# myGlasses.net
KiCad netlist of a schematic drawn in EAGLE
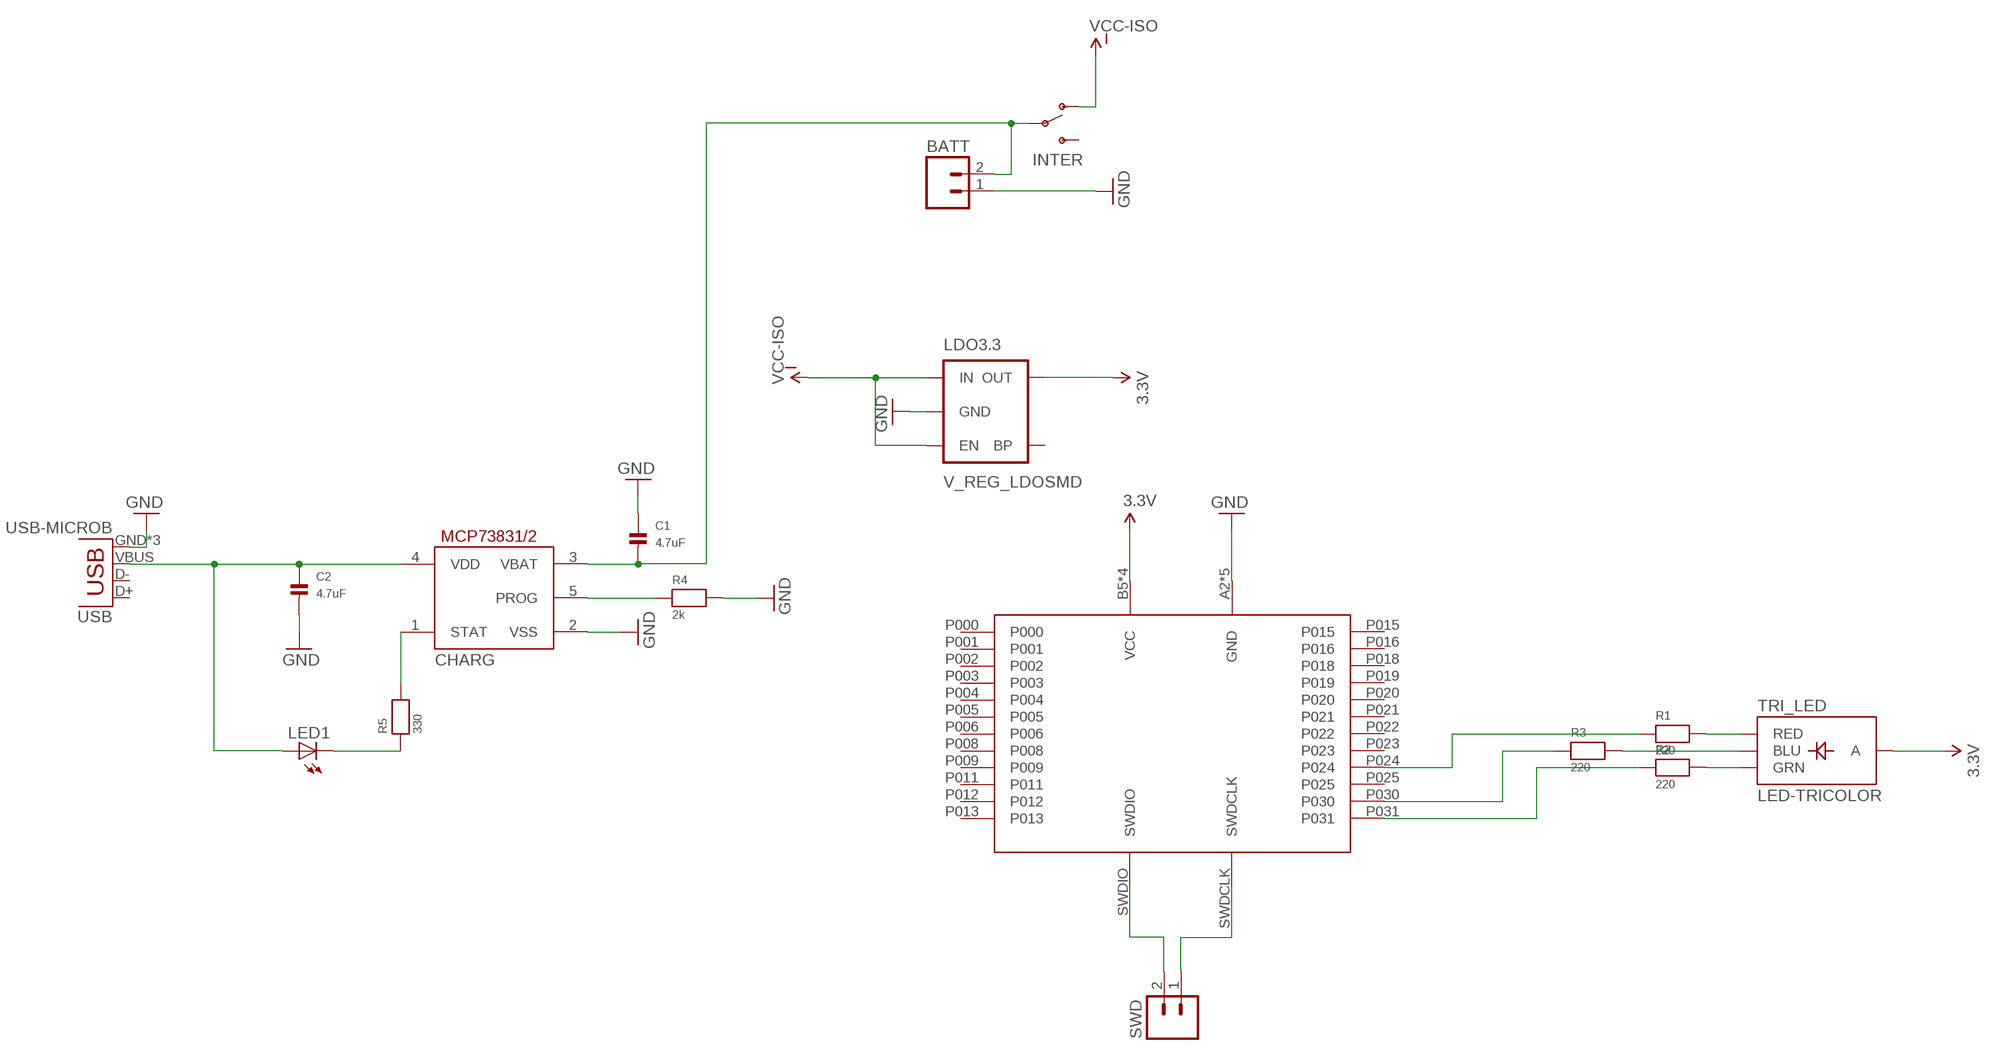
[diagram p0: schematic, sheet 1]

(export (version "E")
  (design (tool "Eeschema 10.0.6"))
  (components
    (comp (ref "BATT")
      (value "M02PTH3")
      (footprint "eagle-import:1X02_LONGPADS")
      (libsource (lib "eagle-import") (part "M02PTH3"))
    )
    (comp (ref "C1")
      (value "4.7uF")
      (footprint "eagle-import:1206")
      (libsource (lib "eagle-import") (part "CAP_CERAMIC1206"))
    )
    (comp (ref "C2")
      (value "4.7uF")
      (footprint "eagle-import:1206")
      (libsource (lib "eagle-import") (part "CAP_CERAMIC1206"))
    )
    (comp (ref "CHARG")
      (value "MCP73831/OT")
      (footprint "eagle-import:SOT23-5L")
      (libsource (lib "eagle-import") (part "MCP73831/OT"))
    )
    (comp (ref "INTER")
      (value "SWITCH-SPDTPTH_LOCK")
      (footprint "eagle-import:SWITCH-SPDT_LOCK.007S")
      (libsource (lib "eagle-import") (part "SWITCH-SPDTPTH_LOCK"))
    )
    (comp (ref "LDO3.3")
      (value "V_REG_LDOSMD")
      (footprint "eagle-import:SOT23-5")
      (libsource (lib "eagle-import") (part "V_REG_LDOSMD"))
    )
    (comp (ref "LED1")
      (value "LEDCHIPLED_1206")
      (footprint "eagle-import:CHIPLED_1206")
      (libsource (lib "eagle-import") (part "LEDCHIPLED_1206"))
    )
    (comp (ref "N550")
      (value "N548")
      (footprint "eagle-import:N548")
      (libsource (lib "eagle-import") (part "N548"))
    )
    (comp (ref "R1")
      (value "220")
      (footprint "eagle-import:1206")
      (libsource (lib "eagle-import") (part "RESISTOR1206"))
    )
    (comp (ref "R2")
      (value "220")
      (footprint "eagle-import:1206")
      (libsource (lib "eagle-import") (part "RESISTOR1206"))
    )
    (comp (ref "R3")
      (value "220")
      (footprint "eagle-import:1206")
      (libsource (lib "eagle-import") (part "RESISTOR1206"))
    )
    (comp (ref "R4")
      (value "2k")
      (footprint "eagle-import:1206")
      (libsource (lib "eagle-import") (part "RESISTOR1206"))
    )
    (comp (ref "R5")
      (value "330")
      (footprint "eagle-import:1206")
      (libsource (lib "eagle-import") (part "RESISTOR1206"))
    )
    (comp (ref "SWD")
      (value "M02PTH")
      (footprint "eagle-import:1X02")
      (libsource (lib "eagle-import") (part "M02PTH"))
    )
    (comp (ref "TRI_LED")
      (value "LED-TRICOLOR")
      (footprint "eagle-import:LED-TRICOLOR-SMD")
      (libsource (lib "eagle-import") (part "LED-TRICOLOR"))
    )
    (comp (ref "USB")
      (value "USB-MICROB")
      (footprint "eagle-import:USB-MICROB")
      (libsource (lib "eagle-import") (part "USB-MICROB"))
    )
  )
  (nets
    (net (code "1") (name "3.3V") (class "Default")
      (node (ref "LDO3.3") (pin "5") (pinfunction "OUT_5") (pintype "passive"))
      (node (ref "N550") (pin "B5") (pinfunction "VCC_B5") (pintype "bidirectional"))
      (node (ref "N550") (pin "B6") (pinfunction "VCC_B6") (pintype "bidirectional"))
      (node (ref "N550") (pin "C5") (pinfunction "VCC_C5") (pintype "bidirectional"))
      (node (ref "N550") (pin "C6") (pinfunction "VCC_C6") (pintype "bidirectional"))
      (node (ref "TRI_LED") (pin "A") (pinfunction "A_A") (pintype "bidirectional"))
    )
    (net (code "2") (name "GND") (class "Default")
      (node (ref "BATT") (pin "1") (pinfunction "1_1") (pintype "passive"))
      (node (ref "C1") (pin "1") (pinfunction "P$1_1") (pintype "passive"))
      (node (ref "C2") (pin "2") (pinfunction "P$2_2") (pintype "passive"))
      (node (ref "CHARG") (pin "2") (pinfunction "VSS_2") (pintype "power_in"))
      (node (ref "LDO3.3") (pin "2") (pinfunction "GND_2") (pintype "input"))
      (node (ref "N550") (pin "A2") (pinfunction "GND_A2") (pintype "bidirectional"))
      (node (ref "N550") (pin "A3") (pinfunction "GND_A3") (pintype "bidirectional"))
      (node (ref "N550") (pin "A4") (pinfunction "GND_A4") (pintype "bidirectional"))
      (node (ref "N550") (pin "A5") (pinfunction "GND_A5") (pintype "bidirectional"))
      (node (ref "N550") (pin "A6") (pinfunction "GND_A6") (pintype "bidirectional"))
      (node (ref "R4") (pin "2") (pinfunction "2_2") (pintype "passive"))
      (node (ref "USB") (pin "GND") (pinfunction "GND_GND") (pintype "bidirectional"))
      (node (ref "USB") (pin "MT1") (pinfunction "GND_MT1") (pintype "bidirectional"))
      (node (ref "USB") (pin "MT2") (pinfunction "GND_MT2") (pintype "bidirectional"))
    )
    (net (code "3") (name "Net-(C1-P$2)") (class "Default")
      (node (ref "BATT") (pin "2") (pinfunction "2_2") (pintype "passive"))
      (node (ref "C1") (pin "2") (pinfunction "P$2_2") (pintype "passive"))
      (node (ref "CHARG") (pin "3") (pinfunction "VBAT_3") (pintype "bidirectional"))
      (node (ref "INTER") (pin "2") (pinfunction "P_2") (pintype "passive"))
    )
    (net (code "4") (name "Net-(C2-P$1)") (class "Default")
      (node (ref "C2") (pin "1") (pinfunction "P$1_1") (pintype "passive"))
      (node (ref "CHARG") (pin "4") (pinfunction "VDD_4") (pintype "power_in"))
      (node (ref "LED1") (pin "A") (pinfunction "A_A") (pintype "passive"))
      (node (ref "USB") (pin "VBUS") (pinfunction "VBUS_VBUS") (pintype "bidirectional"))
    )
    (net (code "5") (name "Net-(CHARG-PROG)") (class "Default")
      (node (ref "CHARG") (pin "5") (pinfunction "PROG_5") (pintype "input"))
      (node (ref "R4") (pin "1") (pinfunction "1_1") (pintype "passive"))
    )
    (net (code "6") (name "Net-(CHARG-STAT)") (class "Default")
      (node (ref "CHARG") (pin "1") (pinfunction "STAT_1") (pintype "output"))
      (node (ref "R5") (pin "2") (pinfunction "2_2") (pintype "passive"))
    )
    (net (code "7") (name "Net-(LED1-PadC)") (class "Default")
      (node (ref "LED1") (pin "C") (pinfunction "C_C") (pintype "passive"))
      (node (ref "R5") (pin "1") (pinfunction "1_1") (pintype "passive"))
    )
    (net (code "8") (name "Net-(N550-PadP024)") (class "Default")
      (node (ref "N550") (pin "P024") (pinfunction "P024_P024") (pintype "bidirectional"))
      (node (ref "R1") (pin "1") (pinfunction "1_1") (pintype "passive"))
    )
    (net (code "9") (name "Net-(N550-PadP030)") (class "Default")
      (node (ref "N550") (pin "P030") (pinfunction "P030_P030") (pintype "bidirectional"))
      (node (ref "R3") (pin "1") (pinfunction "1_1") (pintype "passive"))
    )
    (net (code "10") (name "Net-(N550-PadP031)") (class "Default")
      (node (ref "N550") (pin "P031") (pinfunction "P031_P031") (pintype "bidirectional"))
      (node (ref "R2") (pin "1") (pinfunction "1_1") (pintype "passive"))
    )
    (net (code "11") (name "Net-(N550-PadSWDCLK)") (class "Default")
      (node (ref "N550") (pin "SWDCLK") (pinfunction "SWDCLK_SWDCLK") (pintype "bidirectional"))
      (node (ref "SWD") (pin "1") (pinfunction "1_1") (pintype "passive"))
    )
    (net (code "12") (name "Net-(N550-PadSWDIO)") (class "Default")
      (node (ref "N550") (pin "SWDIO") (pinfunction "SWDIO_SWDIO") (pintype "bidirectional"))
      (node (ref "SWD") (pin "2") (pinfunction "2_2") (pintype "passive"))
    )
    (net (code "13") (name "Net-(TRI_LED-BLU)") (class "Default")
      (node (ref "R3") (pin "2") (pinfunction "2_2") (pintype "passive"))
      (node (ref "TRI_LED") (pin "B") (pinfunction "BLU_B") (pintype "bidirectional"))
    )
    (net (code "14") (name "Net-(TRI_LED-GRN)") (class "Default")
      (node (ref "R2") (pin "2") (pinfunction "2_2") (pintype "passive"))
      (node (ref "TRI_LED") (pin "G") (pinfunction "GRN_G") (pintype "bidirectional"))
    )
    (net (code "15") (name "Net-(TRI_LED-RED)") (class "Default")
      (node (ref "R1") (pin "2") (pinfunction "2_2") (pintype "passive"))
      (node (ref "TRI_LED") (pin "R") (pinfunction "RED_R") (pintype "bidirectional"))
    )
    (net (code "16") (name "VCC-ISO") (class "Default")
      (node (ref "INTER") (pin "1") (pinfunction "O_1") (pintype "passive"))
      (node (ref "LDO3.3") (pin "1") (pinfunction "IN_1") (pintype "input"))
      (node (ref "LDO3.3") (pin "3") (pinfunction "EN_3") (pintype "input"))
    )
    (net (code "17") (name "unconnected-(INTER-S-Pad3)") (class "Default")
      (node (ref "INTER") (pin "3") (pinfunction "S_3") (pintype "passive"))
    )
    (net (code "18") (name "unconnected-(LDO3.3-BP-Pad4)") (class "Default")
      (node (ref "LDO3.3") (pin "4") (pinfunction "BP_4") (pintype "input"))
    )
    (net (code "19") (name "unconnected-(N550-PadP000)") (class "Default")
      (node (ref "N550") (pin "P000") (pinfunction "P000_P000") (pintype "bidirectional"))
    )
    (net (code "20") (name "unconnected-(N550-PadP001)") (class "Default")
      (node (ref "N550") (pin "P001") (pinfunction "P001_P001") (pintype "bidirectional"))
    )
    (net (code "21") (name "unconnected-(N550-PadP002)") (class "Default")
      (node (ref "N550") (pin "P002") (pinfunction "P002_P002") (pintype "bidirectional"))
    )
    (net (code "22") (name "unconnected-(N550-PadP003)") (class "Default")
      (node (ref "N550") (pin "P003") (pinfunction "P003_P003") (pintype "bidirectional"))
    )
    (net (code "23") (name "unconnected-(N550-PadP004)") (class "Default")
      (node (ref "N550") (pin "P004") (pinfunction "P004_P004") (pintype "bidirectional"))
    )
    (net (code "24") (name "unconnected-(N550-PadP005)") (class "Default")
      (node (ref "N550") (pin "P005") (pinfunction "P005_P005") (pintype "bidirectional"))
    )
    (net (code "25") (name "unconnected-(N550-PadP006)") (class "Default")
      (node (ref "N550") (pin "P006") (pinfunction "P006_P006") (pintype "bidirectional"))
    )
    (net (code "26") (name "unconnected-(N550-PadP008)") (class "Default")
      (node (ref "N550") (pin "P008") (pinfunction "P008_P008") (pintype "bidirectional"))
    )
    (net (code "27") (name "unconnected-(N550-PadP009)") (class "Default")
      (node (ref "N550") (pin "P009") (pinfunction "P009_P009") (pintype "bidirectional"))
    )
    (net (code "28") (name "unconnected-(N550-PadP011)") (class "Default")
      (node (ref "N550") (pin "P011") (pinfunction "P011_P011") (pintype "bidirectional"))
    )
    (net (code "29") (name "unconnected-(N550-PadP012)") (class "Default")
      (node (ref "N550") (pin "P012") (pinfunction "P012_P012") (pintype "bidirectional"))
    )
    (net (code "30") (name "unconnected-(N550-PadP013)") (class "Default")
      (node (ref "N550") (pin "P013") (pinfunction "P013_P013") (pintype "bidirectional"))
    )
    (net (code "31") (name "unconnected-(N550-PadP015)") (class "Default")
      (node (ref "N550") (pin "P015") (pinfunction "P015_P015") (pintype "bidirectional"))
    )
    (net (code "32") (name "unconnected-(N550-PadP016)") (class "Default")
      (node (ref "N550") (pin "P016") (pinfunction "P016_P016") (pintype "bidirectional"))
    )
    (net (code "33") (name "unconnected-(N550-PadP018)") (class "Default")
      (node (ref "N550") (pin "P018") (pinfunction "P018_P018") (pintype "bidirectional"))
    )
    (net (code "34") (name "unconnected-(N550-PadP019)") (class "Default")
      (node (ref "N550") (pin "P019") (pinfunction "P019_P019") (pintype "bidirectional"))
    )
    (net (code "35") (name "unconnected-(N550-PadP020)") (class "Default")
      (node (ref "N550") (pin "P020") (pinfunction "P020_P020") (pintype "bidirectional"))
    )
    (net (code "36") (name "unconnected-(N550-PadP021)") (class "Default")
      (node (ref "N550") (pin "P021") (pinfunction "P021_P021") (pintype "bidirectional"))
    )
    (net (code "37") (name "unconnected-(N550-PadP022)") (class "Default")
      (node (ref "N550") (pin "P022") (pinfunction "P022_P022") (pintype "bidirectional"))
    )
    (net (code "38") (name "unconnected-(N550-PadP023)") (class "Default")
      (node (ref "N550") (pin "P023") (pinfunction "P023_P023") (pintype "bidirectional"))
    )
    (net (code "39") (name "unconnected-(N550-PadP025)") (class "Default")
      (node (ref "N550") (pin "P025") (pinfunction "P025_P025") (pintype "bidirectional"))
    )
    (net (code "40") (name "unconnected-(USB-PadD+)") (class "Default")
      (node (ref "USB") (pin "D+") (pinfunction "D+_D+") (pintype "bidirectional"))
    )
    (net (code "41") (name "unconnected-(USB-PadD-)") (class "Default")
      (node (ref "USB") (pin "D-") (pinfunction "D-_D-") (pintype "bidirectional"))
    )
  )
)
